# Boost_Conv_V1_0_Power_Sch.net
KiCad netlist of a schematic drawn in Altium Designer
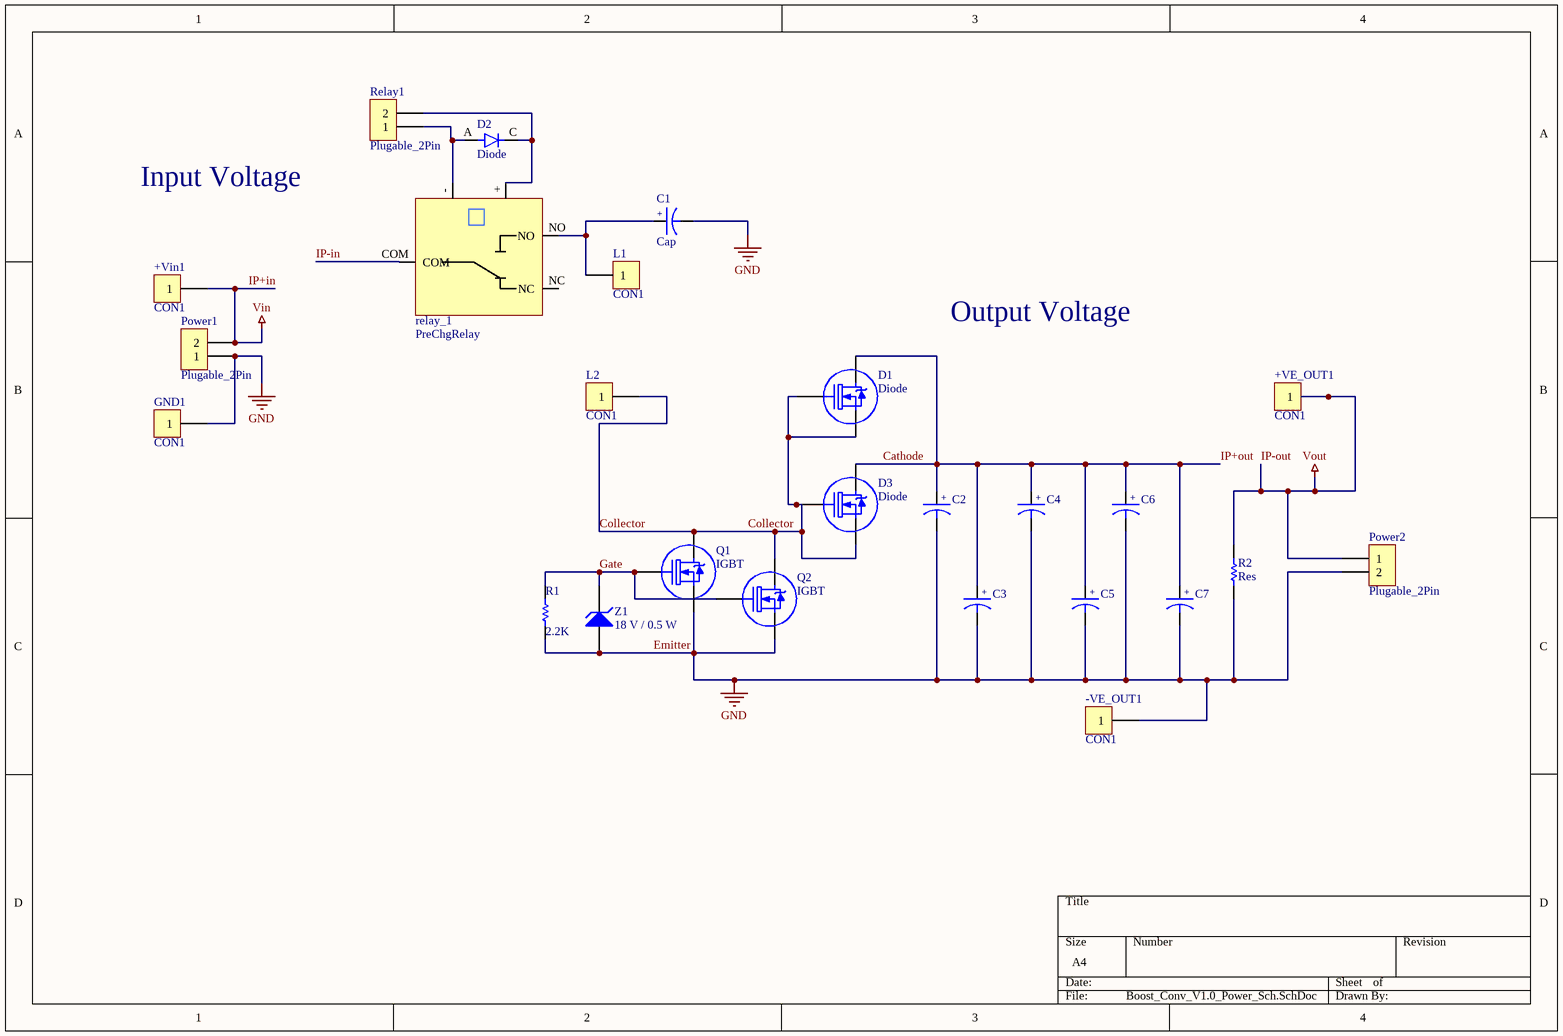
[diagram p0: Boost_Conv_V1.0_Power_Sch.SchDoc]

(export (version "E")
  (design (tool "Eeschema 10.0.6"))
  (components
    (comp (ref "+VE_OUT1")
      (value "CON1")
      (footprint "WIRE6MM")
      (description "Connector")
      (libsource (lib "Sigma_Library") (part "CON1"))
    )
    (comp (ref "+Vin1")
      (value "CON1")
      (footprint "WIRE6MM")
      (description "Connector")
      (libsource (lib "Sigma_Library") (part "CON1"))
    )
    (comp (ref "-VE_OUT1")
      (value "CON1")
      (footprint "WIRE6MM")
      (description "Connector")
      (libsource (lib "Sigma_Library") (part "CON1"))
    )
    (comp (ref "C1")
      (value "Cap")
      (footprint "DC-CAPACITOR")
      (description "Electrolytic Capacitors")
      (libsource (lib "Booster") (part "CAPACITOR POL"))
    )
    (comp (ref "C2")
      (value "Cap")
      (footprint "DC-CAPACITOR")
      (description "Electrolytic Capacitors")
      (libsource (lib "Booster") (part "CAPACITOR POL"))
    )
    (comp (ref "C3")
      (value "Cap")
      (footprint "DC-CAPACITOR")
      (description "Electrolytic Capacitors")
      (libsource (lib "Booster") (part "CAPACITOR POL"))
    )
    (comp (ref "C4")
      (value "Cap")
      (footprint "DC-CAPACITOR")
      (description "Electrolytic Capacitors")
      (libsource (lib "Booster") (part "CAPACITOR POL"))
    )
    (comp (ref "C5")
      (value "Cap")
      (footprint "DC-CAPACITOR")
      (description "Electrolytic Capacitors")
      (libsource (lib "Booster") (part "CAPACITOR POL"))
    )
    (comp (ref "C6")
      (value "Cap")
      (footprint "DC-CAPACITOR")
      (description "Electrolytic Capacitors")
      (libsource (lib "Booster") (part "CAPACITOR POL"))
    )
    (comp (ref "C7")
      (value "Cap")
      (footprint "DC-CAPACITOR")
      (description "Electrolytic Capacitors")
      (libsource (lib "Booster") (part "CAPACITOR POL"))
    )
    (comp (ref "D1")
      (value "Diode")
      (footprint "Sigma_Library:To220")
      (description "N-Channel MOSFET")
      (fields (field (name "PUBLISHER") "Altium Limited"))
      (libsource (lib "Sigma_Library") (part "IRF540N"))
    )
    (comp (ref "D2")
      (value "Diode")
      (footprint "DIOAD1060W80L520D270")
      (description "Diode Standard 1000 V 1A Through Hole Axial")
      (fields (field (name "MP") "1N4007RL") (field (name "MF") "ON Semiconductor"))
      (libsource (lib "Altuim_Sch_Lib") (part "1N4007RL"))
    )
    (comp (ref "D3")
      (value "Diode")
      (footprint "Sigma_Library:To220")
      (description "N-Channel MOSFET")
      (fields (field (name "PUBLISHER") "Altium Limited"))
      (libsource (lib "Sigma_Library") (part "IRF540N"))
    )
    (comp (ref "GND1")
      (value "CON1")
      (footprint "WIRE6MM")
      (description "Connector")
      (libsource (lib "Sigma_Library") (part "CON1"))
    )
    (comp (ref "L1")
      (value "CON1")
      (footprint "WIRE6MM")
      (description "Connector")
      (libsource (lib "") (part "CON1_1"))
    )
    (comp (ref "L2")
      (value "CON1")
      (footprint "WIRE6MM")
      (description "Connector")
      (libsource (lib "Sigma_Library") (part "CON1"))
    )
    (comp (ref "Power1")
      (value "Plugable_2Pin")
      (footprint "Sigma_Library:TB2")
      (description "Connector")
      (libsource (lib "Sigma_Library") (part "CON2"))
    )
    (comp (ref "Power2")
      (value "Plugable_2Pin")
      (footprint "Sigma_Library:TB2")
      (description "Connector")
      (libsource (lib "") (part "CON2_1"))
    )
    (comp (ref "Q1")
      (value "IGBT")
      (footprint "TO247")
      (description "N-Channel MOSFET")
      (fields (field (name "PUBLISHER") "Altium Limited"))
      (libsource (lib "Sigma_Library") (part "IRF540N"))
    )
    (comp (ref "Q2")
      (value "IGBT")
      (footprint "TO247")
      (description "N-Channel MOSFET")
      (fields (field (name "PUBLISHER") "Altium Limited"))
      (libsource (lib "Sigma_Library") (part "IRF540N"))
    )
    (comp (ref "R1")
      (value "2.2K")
      (footprint "AXIAL-0.3")
      (description "Resistor")
      (fields (field (name "Comment") "Res1") (field (name "PUBLISHER") "Altium Limited"))
      (libsource (lib "Miscellaneous Devices") (part "Res1"))
    )
    (comp (ref "R2")
      (value "Res")
      (footprint "Sigma_Library:R600")
      (description "Resistor")
      (libsource (lib "Sigma_Library") (part "Res1"))
    )
    (comp (ref "Relay1")
      (value "Plugable_2Pin")
      (footprint "Sigma_Library:TB2")
      (description "Connector")
      (libsource (lib "Sigma_Library") (part "CON2"))
    )
    (comp (ref "relay_1")
      (value "PreChgRelay")
      (footprint "NT90TNCS12CB")
      (description "NT90THLCE12CB")
      (libsource (lib "Schlib-DC-LINK") (part "PreChgRelay"))
    )
    (comp (ref "Z1")
      (value "18 V / 0.5 W")
      (footprint "Sigma_Library:D3")
      (description "Zener diode")
      (libsource (lib "Sigma_Library") (part "Zener_Diode"))
    )
  )
  (nets
    (net (code "1") (name "/Cathode") (class "Default")
      (node (ref "C2") (pin "1") (pinfunction "1_1") (pintype "passive"))
      (node (ref "C3") (pin "1") (pinfunction "1_1") (pintype "passive"))
      (node (ref "C4") (pin "1") (pinfunction "1_1") (pintype "passive"))
      (node (ref "C5") (pin "1") (pinfunction "1_1") (pintype "passive"))
      (node (ref "C6") (pin "1") (pinfunction "1_1") (pintype "passive"))
      (node (ref "C7") (pin "1") (pinfunction "1_1") (pintype "passive"))
      (node (ref "D1") (pin "2") (pinfunction "D_2") (pintype "passive"))
      (node (ref "D3") (pin "2") (pinfunction "D_2") (pintype "passive"))
    )
    (net (code "2") (name "/Collector") (class "Default")
      (node (ref "D1") (pin "1") (pinfunction "G_1") (pintype "passive"))
      (node (ref "D1") (pin "3") (pinfunction "S_3") (pintype "passive"))
      (node (ref "D3") (pin "1") (pinfunction "G_1") (pintype "passive"))
      (node (ref "D3") (pin "3") (pinfunction "S_3") (pintype "passive"))
      (node (ref "L2") (pin "1") (pinfunction "1_1") (pintype "passive"))
      (node (ref "Q1") (pin "2") (pinfunction "D_2") (pintype "passive"))
      (node (ref "Q2") (pin "2") (pinfunction "D_2") (pintype "passive"))
    )
    (net (code "3") (name "/Gate") (class "Default")
      (node (ref "Q1") (pin "1") (pinfunction "G_1") (pintype "passive"))
      (node (ref "Q2") (pin "1") (pinfunction "G_1") (pintype "passive"))
      (node (ref "R1") (pin "2") (pinfunction "2_2") (pintype "passive"))
      (node (ref "Z1") (pin "K") (pinfunction "K_K") (pintype "passive"))
    )
    (net (code "4") (name "/IP-in") (class "Default")
      (node (ref "relay_1") (pin "COM") (pinfunction "COM_COM") (pintype "passive"))
    )
    (net (code "5") (name "GND") (class "Default")
      (node (ref "-VE_OUT1") (pin "1") (pinfunction "1_1") (pintype "passive"))
      (node (ref "C1") (pin "2") (pinfunction "2_2") (pintype "passive"))
      (node (ref "C2") (pin "2") (pinfunction "2_2") (pintype "passive"))
      (node (ref "C3") (pin "2") (pinfunction "2_2") (pintype "passive"))
      (node (ref "C4") (pin "2") (pinfunction "2_2") (pintype "passive"))
      (node (ref "C5") (pin "2") (pinfunction "2_2") (pintype "passive"))
      (node (ref "C6") (pin "2") (pinfunction "2_2") (pintype "passive"))
      (node (ref "C7") (pin "2") (pinfunction "2_2") (pintype "passive"))
      (node (ref "GND1") (pin "1") (pinfunction "1_1") (pintype "passive"))
      (node (ref "Power1") (pin "1") (pinfunction "1_1") (pintype "passive"))
      (node (ref "Power2") (pin "2") (pinfunction "2_2") (pintype "passive"))
      (node (ref "Q1") (pin "3") (pinfunction "S_3") (pintype "passive"))
      (node (ref "Q2") (pin "3") (pinfunction "S_3") (pintype "passive"))
      (node (ref "R1") (pin "1") (pinfunction "1_1") (pintype "passive"))
      (node (ref "R2") (pin "1") (pinfunction "1_1") (pintype "passive"))
      (node (ref "Z1") (pin "A") (pinfunction "A_A") (pintype "passive"))
    )
    (net (code "6") (name "Net-(C1-Pad1)") (class "Default")
      (node (ref "C1") (pin "1") (pinfunction "1_1") (pintype "passive"))
      (node (ref "L1") (pin "1") (pinfunction "1_1") (pintype "passive"))
      (node (ref "relay_1") (pin "NO") (pinfunction "NO_NO") (pintype "passive"))
    )
    (net (code "7") (name "Net-(D2-PadA)") (class "Default")
      (node (ref "D2") (pin "A") (pinfunction "A_A") (pintype "passive"))
      (node (ref "Relay1") (pin "1") (pinfunction "1_1") (pintype "passive"))
      (node (ref "relay_1") (pin "-") (pintype "passive"))
    )
    (net (code "8") (name "Net-(D2-PadC)") (class "Default")
      (node (ref "D2") (pin "C") (pinfunction "C_C") (pintype "passive"))
      (node (ref "Relay1") (pin "2") (pinfunction "2_2") (pintype "passive"))
      (node (ref "relay_1") (pin "+") (pintype "passive"))
    )
    (net (code "9") (name "Vin") (class "Default")
      (node (ref "+Vin1") (pin "1") (pinfunction "1_1") (pintype "passive"))
      (node (ref "Power1") (pin "2") (pinfunction "2_2") (pintype "passive"))
    )
    (net (code "10") (name "Vout") (class "Default")
      (node (ref "+VE_OUT1") (pin "1") (pinfunction "1_1") (pintype "passive"))
      (node (ref "Power2") (pin "1") (pinfunction "1_1") (pintype "passive"))
      (node (ref "R2") (pin "2") (pinfunction "2_2") (pintype "passive"))
    )
    (net (code "11") (name "unconnected-(relay_1-PadNC)") (class "Default")
      (node (ref "relay_1") (pin "NC") (pinfunction "NC_NC") (pintype "passive"))
    )
  )
)
